# hv-testbench-schematic.net
KiCad netlist of a schematic drawn in EasyEDA
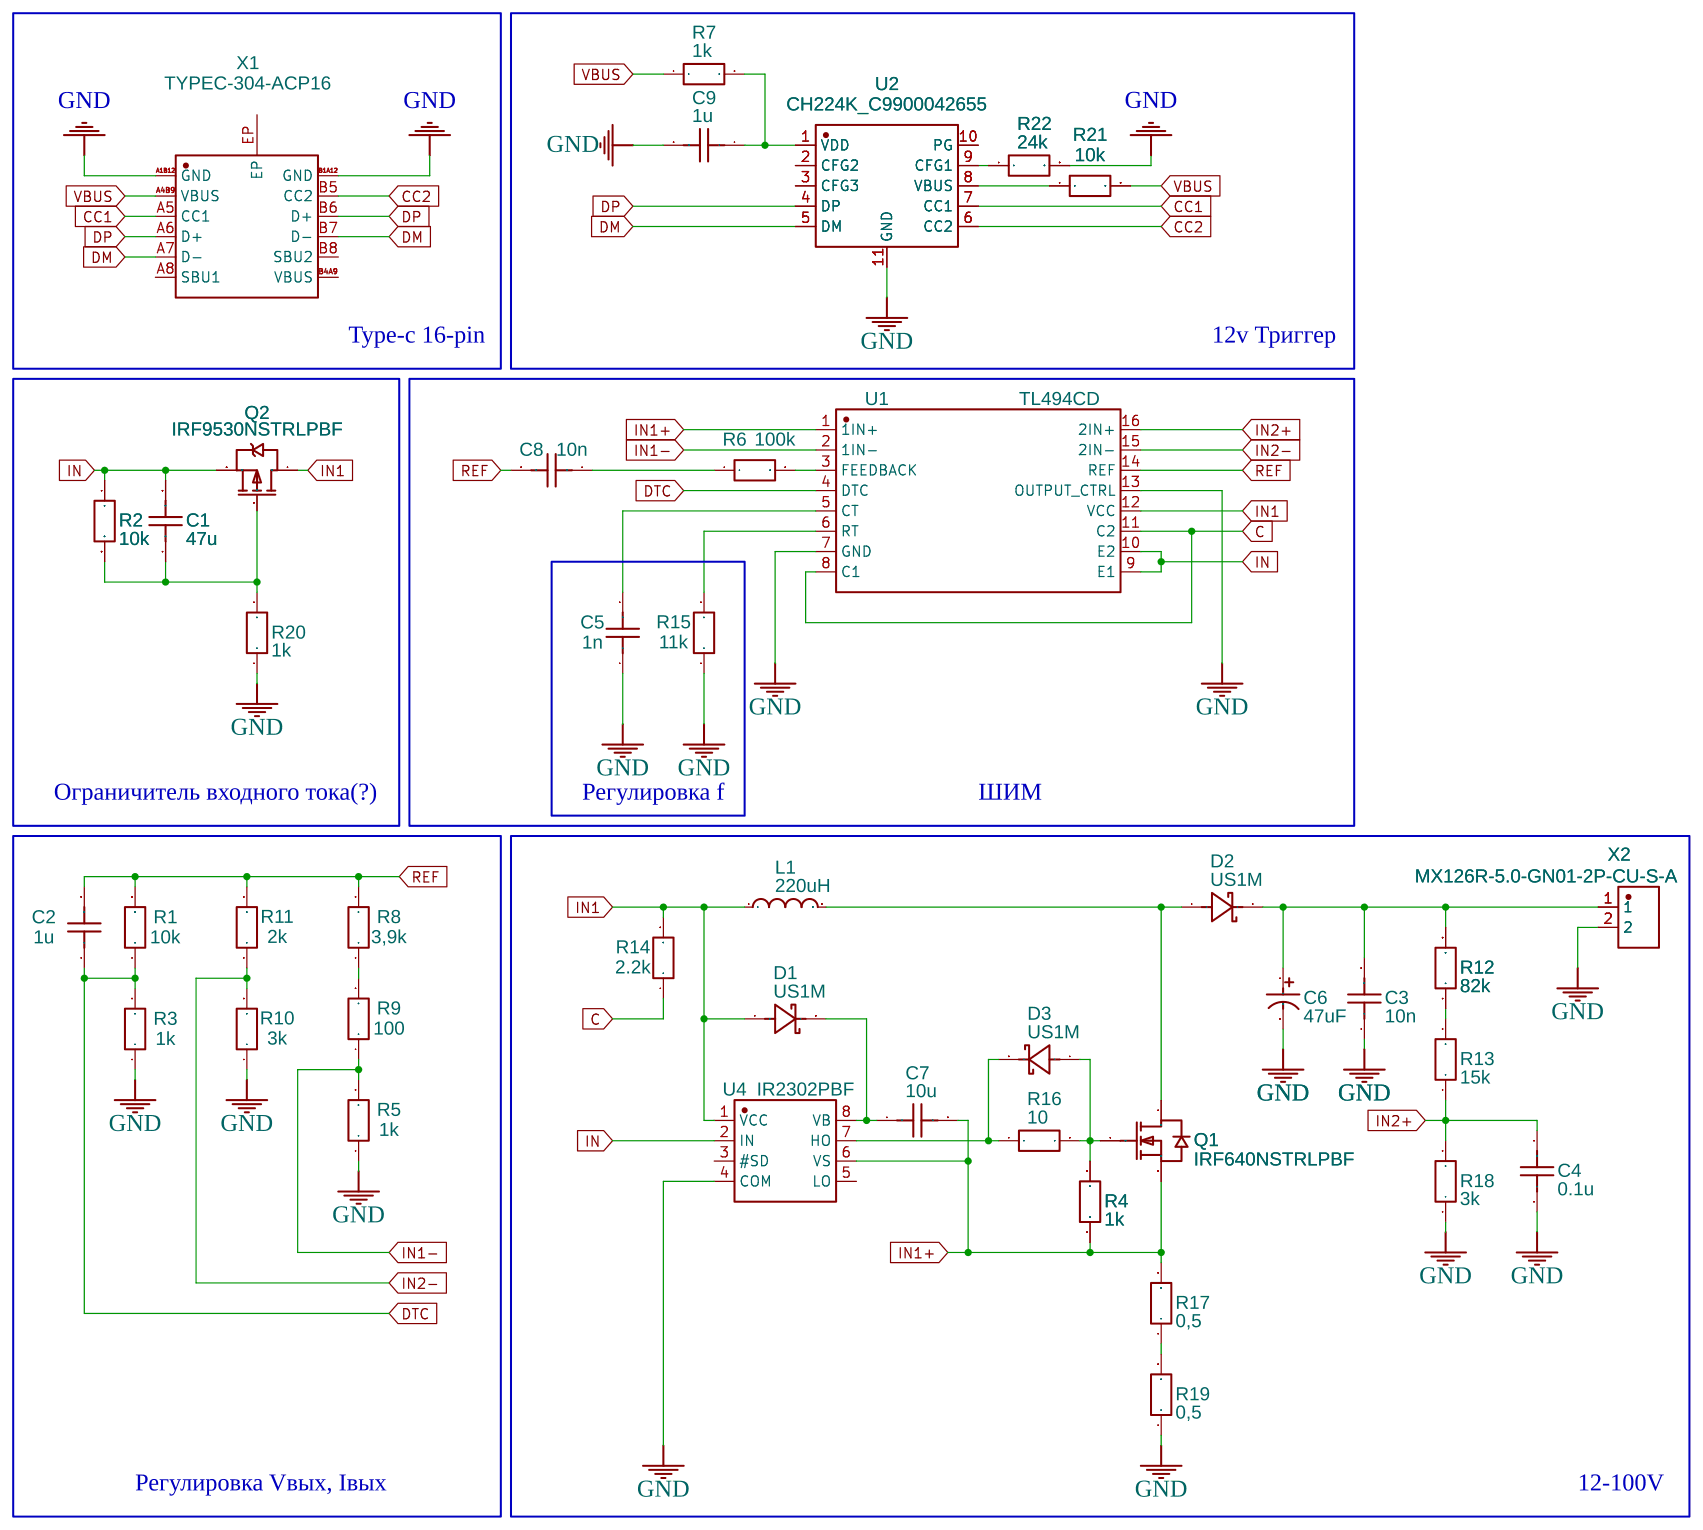
[diagram p0: schematic sheet]

(export (version "E")
  (design (tool "Eeschema 10.0.6"))
  (components
    (comp (ref "C1") (value "47u") (libsource (lib "") (part "C_1206_US")))
    (comp (ref "C2") (value "1u") (libsource (lib "") (part "C_0805_US_2")))
    (comp (ref "C3") (value "10n") (libsource (lib "") (part "C_0805_US_2")))
    (comp (ref "C4") (value "0.1u") (libsource (lib "") (part "C_0805_US_1")))
    (comp (ref "C5") (value "1n") (libsource (lib "") (part "C_0402_US")))
    (comp (ref "C6")
      (value "47uF")
      (fields (field (name "Manufacturer Part") "47uf/250V") (field (name "Manufacturer") "ReliaPro"))
      (libsource (lib "") (part "47uf/250V"))
    )
    (comp (ref "C7") (value "10u") (libsource (lib "") (part "C_0805_US_3")))
    (comp (ref "C8") (value "10n") (libsource (lib "") (part "C_0805_US")))
    (comp (ref "C9") (value "1u") (libsource (lib "") (part "C_0805_US")))
    (comp (ref "D1")
      (value "US1M")
      (fields (field (name "Manufacturer") "R+O(宏嘉诚)"))
      (libsource (lib "") (part "US1M_1"))
    )
    (comp (ref "D2")
      (value "US1M")
      (fields (field (name "Manufacturer") "R+O(宏嘉诚)"))
      (libsource (lib "") (part "US1M_1"))
    )
    (comp (ref "D3")
      (value "US1M")
      (fields (field (name "Manufacturer") "R+O(宏嘉诚)"))
      (libsource (lib "") (part "US1M"))
    )
    (comp (ref "L1")
      (value "220uH")
      (fields (field (name "Manufacturer Part") "B82477P4392M") (field (name "Manufacturer") "TDK"))
      (libsource (lib "") (part "B82477P4392M"))
    )
    (comp (ref "Q1")
      (value "IRF640NSTRLPBF")
      (fields (field (name "Manufacturer") "Infineon(英飞凌)"))
      (libsource (lib "") (part "IRF640NSTRLPBF"))
    )
    (comp (ref "Q2")
      (value "IRF9530NSTRLPBF")
      (fields (field (name "Manufacturer") "Infineon(英飞凌)"))
      (libsource (lib "") (part "IRF9530NSTRLPBF"))
    )
    (comp (ref "R1") (value "10k") (libsource (lib "") (part "R_0805_EU")))
    (comp (ref "R2") (value "10k") (libsource (lib "") (part "R_0805_EU_2")))
    (comp (ref "R3") (value "1k") (libsource (lib "") (part "R_0805_EU")))
    (comp (ref "R4") (value "1k") (libsource (lib "") (part "R_1206_EU_1")))
    (comp (ref "R5") (value "1k") (libsource (lib "") (part "R_0805_EU")))
    (comp (ref "R6") (value "100k") (libsource (lib "") (part "R_0805_EU_1")))
    (comp (ref "R7") (value "1k") (libsource (lib "") (part "R_1206_EU")))
    (comp (ref "R8") (value "3,9k") (libsource (lib "") (part "R_0805_EU")))
    (comp (ref "R9") (value "100") (libsource (lib "") (part "R_0805_EU")))
    (comp (ref "R10") (value "3k") (libsource (lib "") (part "R_0805_EU")))
    (comp (ref "R11") (value "2k") (libsource (lib "") (part "R_0805_EU")))
    (comp (ref "R12") (value "82k") (libsource (lib "") (part "R_1206_EU_1")))
    (comp (ref "R13") (value "15k") (libsource (lib "") (part "R_0805_EU")))
    (comp (ref "R14") (value "2.2k") (libsource (lib "") (part "R_0805_EU")))
    (comp (ref "R15") (value "11k") (libsource (lib "") (part "R_0805_EU")))
    (comp (ref "R16") (value "10") (libsource (lib "") (part "R_1206_EU")))
    (comp (ref "R17") (value "0,5") (libsource (lib "") (part "R_2512_EU")))
    (comp (ref "R18") (value "3k") (libsource (lib "") (part "R_0805_EU")))
    (comp (ref "R19") (value "0,5") (libsource (lib "") (part "R_2512_EU")))
    (comp (ref "R20") (value "1k") (libsource (lib "") (part "R_0805_EU")))
    (comp (ref "R21") (value "10k") (libsource (lib "") (part "R_0805_EU_1")))
    (comp (ref "R22") (value "24k") (libsource (lib "") (part "R_0805_EU_1")))
    (comp (ref "U1")
      (value "TL494CD")
      (fields (field (name "Manufacturer") "TI(德州仪器)"))
      (libsource (lib "") (part "TL494CD"))
    )
    (comp (ref "U2")
      (value "CH224K_C9900042655")
      (fields (field (name "Manufacturer Part") "CH224K"))
      (libsource (lib "") (part "CH224K_C9900042655"))
    )
    (comp (ref "U4")
      (value "IR2302PBF")
      (fields (field (name "Manufacturer") "Infineon(英飞凌)"))
      (libsource (lib "") (part "IR2302PBF"))
    )
    (comp (ref "X1")
      (value "TYPEC-304-ACP16")
      (fields (field (name "Manufacturer") "XUNPU(讯普)"))
      (libsource (lib "") (part "TYPEC-304-ACP16"))
    )
    (comp (ref "X2")
      (value "MX126R-5.0-GN01-2P-CU-S-A")
      (fields
        (field (name "Manufacturer Part") "MX126R-5.0-02P-GN01-Cu-S-A")
        (field (name "Manufacturer") "MAX(迈旭)")
      )
      (libsource (lib "") (part "MX126R-5.0-GN01-2P-CU-S-A"))
    )
  )
  (nets
    (net (code "1") (name "C") (class "Default")
      (node (ref "R14") (pin "1") (pinfunction "1_1") (pintype "unspecified"))
      (node (ref "U1") (pin "11") (pinfunction "C2_11") (pintype "unspecified"))
      (node (ref "U1") (pin "8") (pinfunction "C1_8") (pintype "unspecified"))
    )
    (net (code "2") (name "CC1") (class "Default")
      (node (ref "U2") (pin "7") (pinfunction "CC1_7") (pintype "unspecified"))
      (node (ref "X1") (pin "A5") (pinfunction "CC1_A5") (pintype "unspecified"))
    )
    (net (code "3") (name "CC2") (class "Default")
      (node (ref "U2") (pin "6") (pinfunction "CC2_6") (pintype "unspecified"))
      (node (ref "X1") (pin "B5") (pinfunction "CC2_B5") (pintype "unspecified"))
    )
    (net (code "4") (name "DM") (class "Default")
      (node (ref "U2") (pin "5") (pinfunction "DM_5") (pintype "unspecified"))
      (node (ref "X1") (pin "A7") (pinfunction "D-_A7") (pintype "unspecified"))
      (node (ref "X1") (pin "B7") (pinfunction "D-_B7") (pintype "unspecified"))
    )
    (net (code "5") (name "DP") (class "Default")
      (node (ref "U2") (pin "4") (pinfunction "DP_4") (pintype "unspecified"))
      (node (ref "X1") (pin "A6") (pinfunction "D+_A6") (pintype "unspecified"))
      (node (ref "X1") (pin "B6") (pinfunction "D+_B6") (pintype "unspecified"))
    )
    (net (code "6") (name "DTC") (class "Default")
      (node (ref "C2") (pin "1") (pinfunction "1_1") (pintype "unspecified"))
      (node (ref "R1") (pin "1") (pinfunction "1_1") (pintype "unspecified"))
      (node (ref "R3") (pin "2") (pinfunction "2_2") (pintype "unspecified"))
      (node (ref "U1") (pin "4") (pinfunction "DTC_4") (pintype "unspecified"))
    )
    (net (code "7") (name "GND") (class "Default")
      (node (ref "C3") (pin "1") (pinfunction "1_1") (pintype "unspecified"))
      (node (ref "C4") (pin "2") (pinfunction "2_2") (pintype "unspecified"))
      (node (ref "C5") (pin "1") (pinfunction "1_1") (pintype "unspecified"))
      (node (ref "C6") (pin "2") (pinfunction "2_2") (pintype "input"))
      (node (ref "C9") (pin "2") (pinfunction "2_2") (pintype "unspecified"))
      (node (ref "R10") (pin "1") (pinfunction "1_1") (pintype "unspecified"))
      (node (ref "R15") (pin "1") (pinfunction "1_1") (pintype "unspecified"))
      (node (ref "R18") (pin "1") (pinfunction "1_1") (pintype "unspecified"))
      (node (ref "R19") (pin "1") (pinfunction "1_1") (pintype "unspecified"))
      (node (ref "R20") (pin "1") (pinfunction "1_1") (pintype "unspecified"))
      (node (ref "R22") (pin "2") (pinfunction "2_2") (pintype "unspecified"))
      (node (ref "R3") (pin "1") (pinfunction "1_1") (pintype "unspecified"))
      (node (ref "R5") (pin "1") (pinfunction "1_1") (pintype "unspecified"))
      (node (ref "U1") (pin "13") (pinfunction "OUTPUT_CTRL_13") (pintype "unspecified"))
      (node (ref "U1") (pin "7") (pinfunction "GND_7") (pintype "unspecified"))
      (node (ref "U2") (pin "11") (pinfunction "GND_11") (pintype "unspecified"))
      (node (ref "U4") (pin "4") (pinfunction "COM_4") (pintype "unspecified"))
      (node (ref "X1") (pin "A1B12") (pinfunction "GND_A1B12") (pintype "unspecified"))
      (node (ref "X1") (pin "B1A12") (pinfunction "GND_B1A12") (pintype "unspecified"))
      (node (ref "X2") (pin "2") (pinfunction "2_2") (pintype "unspecified"))
    )
    (net (code "8") (name "IN") (class "Default")
      (node (ref "C1") (pin "2") (pinfunction "2_2") (pintype "unspecified"))
      (node (ref "Q2") (pin "3") (pinfunction "S_3") (pintype "unspecified"))
      (node (ref "R2") (pin "1") (pinfunction "1_1") (pintype "unspecified"))
      (node (ref "U1") (pin "10") (pinfunction "E2_10") (pintype "unspecified"))
      (node (ref "U1") (pin "9") (pinfunction "E1_9") (pintype "unspecified"))
      (node (ref "U4") (pin "2") (pinfunction "IN_2") (pintype "unspecified"))
    )
    (net (code "9") (name "IN1") (class "Default")
      (node (ref "D1") (pin "1") (pinfunction "A_1") (pintype "unspecified"))
      (node (ref "L1") (pin "1") (pinfunction "1_1") (pintype "unspecified"))
      (node (ref "Q2") (pin "4") (pinfunction "D_4") (pintype "unspecified"))
      (node (ref "R14") (pin "2") (pinfunction "2_2") (pintype "unspecified"))
      (node (ref "U1") (pin "12") (pinfunction "VCC_12") (pintype "unspecified"))
      (node (ref "U4") (pin "1") (pinfunction "VCC_1") (pintype "unspecified"))
    )
    (net (code "10") (name "IN1+") (class "Default")
      (node (ref "C7") (pin "2") (pinfunction "2_2") (pintype "unspecified"))
      (node (ref "Q1") (pin "3") (pinfunction "S_3") (pintype "unspecified"))
      (node (ref "R17") (pin "2") (pinfunction "2_2") (pintype "unspecified"))
      (node (ref "R4") (pin "1") (pinfunction "1_1") (pintype "unspecified"))
      (node (ref "U1") (pin "1") (pinfunction "1IN+_1") (pintype "unspecified"))
      (node (ref "U4") (pin "6") (pinfunction "VS_6") (pintype "unspecified"))
    )
    (net (code "11") (name "IN1-") (class "Default")
      (node (ref "R5") (pin "2") (pinfunction "2_2") (pintype "unspecified"))
      (node (ref "R9") (pin "1") (pinfunction "1_1") (pintype "unspecified"))
      (node (ref "U1") (pin "2") (pinfunction "1IN−_2") (pintype "unspecified"))
    )
    (net (code "12") (name "IN2+") (class "Default")
      (node (ref "C4") (pin "1") (pinfunction "1_1") (pintype "unspecified"))
      (node (ref "R13") (pin "1") (pinfunction "1_1") (pintype "unspecified"))
      (node (ref "R18") (pin "2") (pinfunction "2_2") (pintype "unspecified"))
      (node (ref "U1") (pin "16") (pinfunction "2IN+_16") (pintype "unspecified"))
    )
    (net (code "13") (name "IN2-") (class "Default")
      (node (ref "R10") (pin "2") (pinfunction "2_2") (pintype "unspecified"))
      (node (ref "R11") (pin "1") (pinfunction "1_1") (pintype "unspecified"))
      (node (ref "U1") (pin "15") (pinfunction "2IN−_15") (pintype "unspecified"))
    )
    (net (code "14") (name "Net-(C8-Pad1)") (class "Default")
      (node (ref "C8") (pin "1") (pinfunction "1_1") (pintype "unspecified"))
      (node (ref "R6") (pin "1") (pinfunction "1_1") (pintype "unspecified"))
    )
    (net (code "15") (name "Net-(D1-K)") (class "Default")
      (node (ref "C7") (pin "1") (pinfunction "1_1") (pintype "unspecified"))
      (node (ref "D1") (pin "2") (pinfunction "K_2") (pintype "unspecified"))
      (node (ref "U4") (pin "8") (pinfunction "VB_8") (pintype "unspecified"))
    )
    (net (code "16") (name "Net-(D2-A)") (class "Default")
      (node (ref "D2") (pin "1") (pinfunction "A_1") (pintype "unspecified"))
      (node (ref "L1") (pin "2") (pinfunction "2_2") (pintype "unspecified"))
      (node (ref "Q1") (pin "4") (pinfunction "D_4") (pintype "unspecified"))
    )
    (net (code "17") (name "Net-(D2-K)") (class "Default")
      (node (ref "C3") (pin "2") (pinfunction "2_2") (pintype "unspecified"))
      (node (ref "C6") (pin "1") (pinfunction "1_1") (pintype "input"))
      (node (ref "D2") (pin "2") (pinfunction "K_2") (pintype "unspecified"))
      (node (ref "R12") (pin "2") (pinfunction "2_2") (pintype "unspecified"))
      (node (ref "X2") (pin "1") (pinfunction "1_1") (pintype "unspecified"))
    )
    (net (code "18") (name "Net-(D3-A)") (class "Default")
      (node (ref "D3") (pin "1") (pinfunction "A_1") (pintype "unspecified"))
      (node (ref "Q1") (pin "1") (pinfunction "G_1") (pintype "unspecified"))
      (node (ref "R16") (pin "2") (pinfunction "2_2") (pintype "unspecified"))
      (node (ref "R4") (pin "2") (pinfunction "2_2") (pintype "unspecified"))
    )
    (net (code "19") (name "Net-(D3-K)") (class "Default")
      (node (ref "D3") (pin "2") (pinfunction "K_2") (pintype "unspecified"))
      (node (ref "R16") (pin "1") (pinfunction "1_1") (pintype "unspecified"))
      (node (ref "U4") (pin "7") (pinfunction "HO_7") (pintype "unspecified"))
    )
    (net (code "20") (name "Net-(Q2-G)") (class "Default")
      (node (ref "C1") (pin "1") (pinfunction "1_1") (pintype "unspecified"))
      (node (ref "Q2") (pin "1") (pinfunction "G_1") (pintype "unspecified"))
      (node (ref "R2") (pin "2") (pinfunction "2_2") (pintype "unspecified"))
      (node (ref "R20") (pin "2") (pinfunction "2_2") (pintype "unspecified"))
    )
    (net (code "21") (name "Net-(R8-Pad1)") (class "Default")
      (node (ref "R8") (pin "1") (pinfunction "1_1") (pintype "unspecified"))
      (node (ref "R9") (pin "2") (pinfunction "2_2") (pintype "unspecified"))
    )
    (net (code "22") (name "Net-(R12-Pad1)") (class "Default")
      (node (ref "R12") (pin "1") (pinfunction "1_1") (pintype "unspecified"))
      (node (ref "R13") (pin "2") (pinfunction "2_2") (pintype "unspecified"))
    )
    (net (code "23") (name "Net-(R17-Pad1)") (class "Default")
      (node (ref "R17") (pin "1") (pinfunction "1_1") (pintype "unspecified"))
      (node (ref "R19") (pin "2") (pinfunction "2_2") (pintype "unspecified"))
    )
    (net (code "24") (name "Net-(U1-CT)") (class "Default")
      (node (ref "C5") (pin "2") (pinfunction "2_2") (pintype "unspecified"))
      (node (ref "U1") (pin "5") (pinfunction "CT_5") (pintype "unspecified"))
    )
    (net (code "25") (name "Net-(U1-FEEDBACK)") (class "Default")
      (node (ref "R6") (pin "2") (pinfunction "2_2") (pintype "unspecified"))
      (node (ref "U1") (pin "3") (pinfunction "FEEDBACK_3") (pintype "unspecified"))
    )
    (net (code "26") (name "Net-(U1-RT)") (class "Default")
      (node (ref "R15") (pin "2") (pinfunction "2_2") (pintype "unspecified"))
      (node (ref "U1") (pin "6") (pinfunction "RT_6") (pintype "unspecified"))
    )
    (net (code "27") (name "Net-(U2-CFG1)") (class "Default")
      (node (ref "R22") (pin "1") (pinfunction "1_1") (pintype "unspecified"))
      (node (ref "U2") (pin "9") (pinfunction "CFG1_9") (pintype "unspecified"))
    )
    (net (code "28") (name "Net-(U2-VBUS)") (class "Default")
      (node (ref "R21") (pin "1") (pinfunction "1_1") (pintype "unspecified"))
      (node (ref "U2") (pin "8") (pinfunction "VBUS_8") (pintype "unspecified"))
    )
    (net (code "29") (name "Net-(U2-VDD)") (class "Default")
      (node (ref "C9") (pin "1") (pinfunction "1_1") (pintype "unspecified"))
      (node (ref "R7") (pin "2") (pinfunction "2_2") (pintype "unspecified"))
      (node (ref "U2") (pin "1") (pinfunction "VDD_1") (pintype "unspecified"))
    )
    (net (code "30") (name "REF") (class "Default")
      (node (ref "C2") (pin "2") (pinfunction "2_2") (pintype "unspecified"))
      (node (ref "C8") (pin "2") (pinfunction "2_2") (pintype "unspecified"))
      (node (ref "R1") (pin "2") (pinfunction "2_2") (pintype "unspecified"))
      (node (ref "R11") (pin "2") (pinfunction "2_2") (pintype "unspecified"))
      (node (ref "R8") (pin "2") (pinfunction "2_2") (pintype "unspecified"))
      (node (ref "U1") (pin "14") (pinfunction "REF_14") (pintype "unspecified"))
    )
    (net (code "31") (name "VBUS") (class "Default")
      (node (ref "R21") (pin "2") (pinfunction "2_2") (pintype "unspecified"))
      (node (ref "R7") (pin "1") (pinfunction "1_1") (pintype "unspecified"))
      (node (ref "X1") (pin "A4B9") (pinfunction "VBUS_A4B9") (pintype "unspecified"))
    )
    (net (code "32") (name "unconnected-(U2-CFG2-Pad2)") (class "Default")
      (node (ref "U2") (pin "2") (pinfunction "CFG2_2") (pintype "unspecified"))
    )
    (net (code "33") (name "unconnected-(U2-CFG3-Pad3)") (class "Default")
      (node (ref "U2") (pin "3") (pinfunction "CFG3_3") (pintype "unspecified"))
    )
    (net (code "34") (name "unconnected-(U2-PG-Pad10)") (class "Default")
      (node (ref "U2") (pin "10") (pinfunction "PG_10") (pintype "unspecified"))
    )
    (net (code "35") (name "unconnected-(U4-#SD-Pad3)") (class "Default")
      (node (ref "U4") (pin "3") (pinfunction "#SD_3") (pintype "unspecified"))
    )
    (net (code "36") (name "unconnected-(U4-LO-Pad5)") (class "Default")
      (node (ref "U4") (pin "5") (pinfunction "LO_5") (pintype "unspecified"))
    )
    (net (code "37") (name "unconnected-(X1-PadEP)") (class "Default")
      (node (ref "X1") (pin "EP") (pinfunction "EP_EP") (pintype "unspecified"))
    )
    (net (code "38") (name "unconnected-(X1-SBU1-PadA8)") (class "Default")
      (node (ref "X1") (pin "A8") (pinfunction "SBU1_A8") (pintype "unspecified"))
    )
    (net (code "39") (name "unconnected-(X1-SBU2-PadB8)") (class "Default")
      (node (ref "X1") (pin "B8") (pinfunction "SBU2_B8") (pintype "unspecified"))
    )
    (net (code "40") (name "unconnected-(X1-VBUS-PadB4A9)") (class "Default")
      (node (ref "X1") (pin "B4A9") (pinfunction "VBUS_B4A9") (pintype "unspecified"))
    )
  )
)
